# V-00808-00.net
KiCad netlist of a schematic drawn in EAGLE
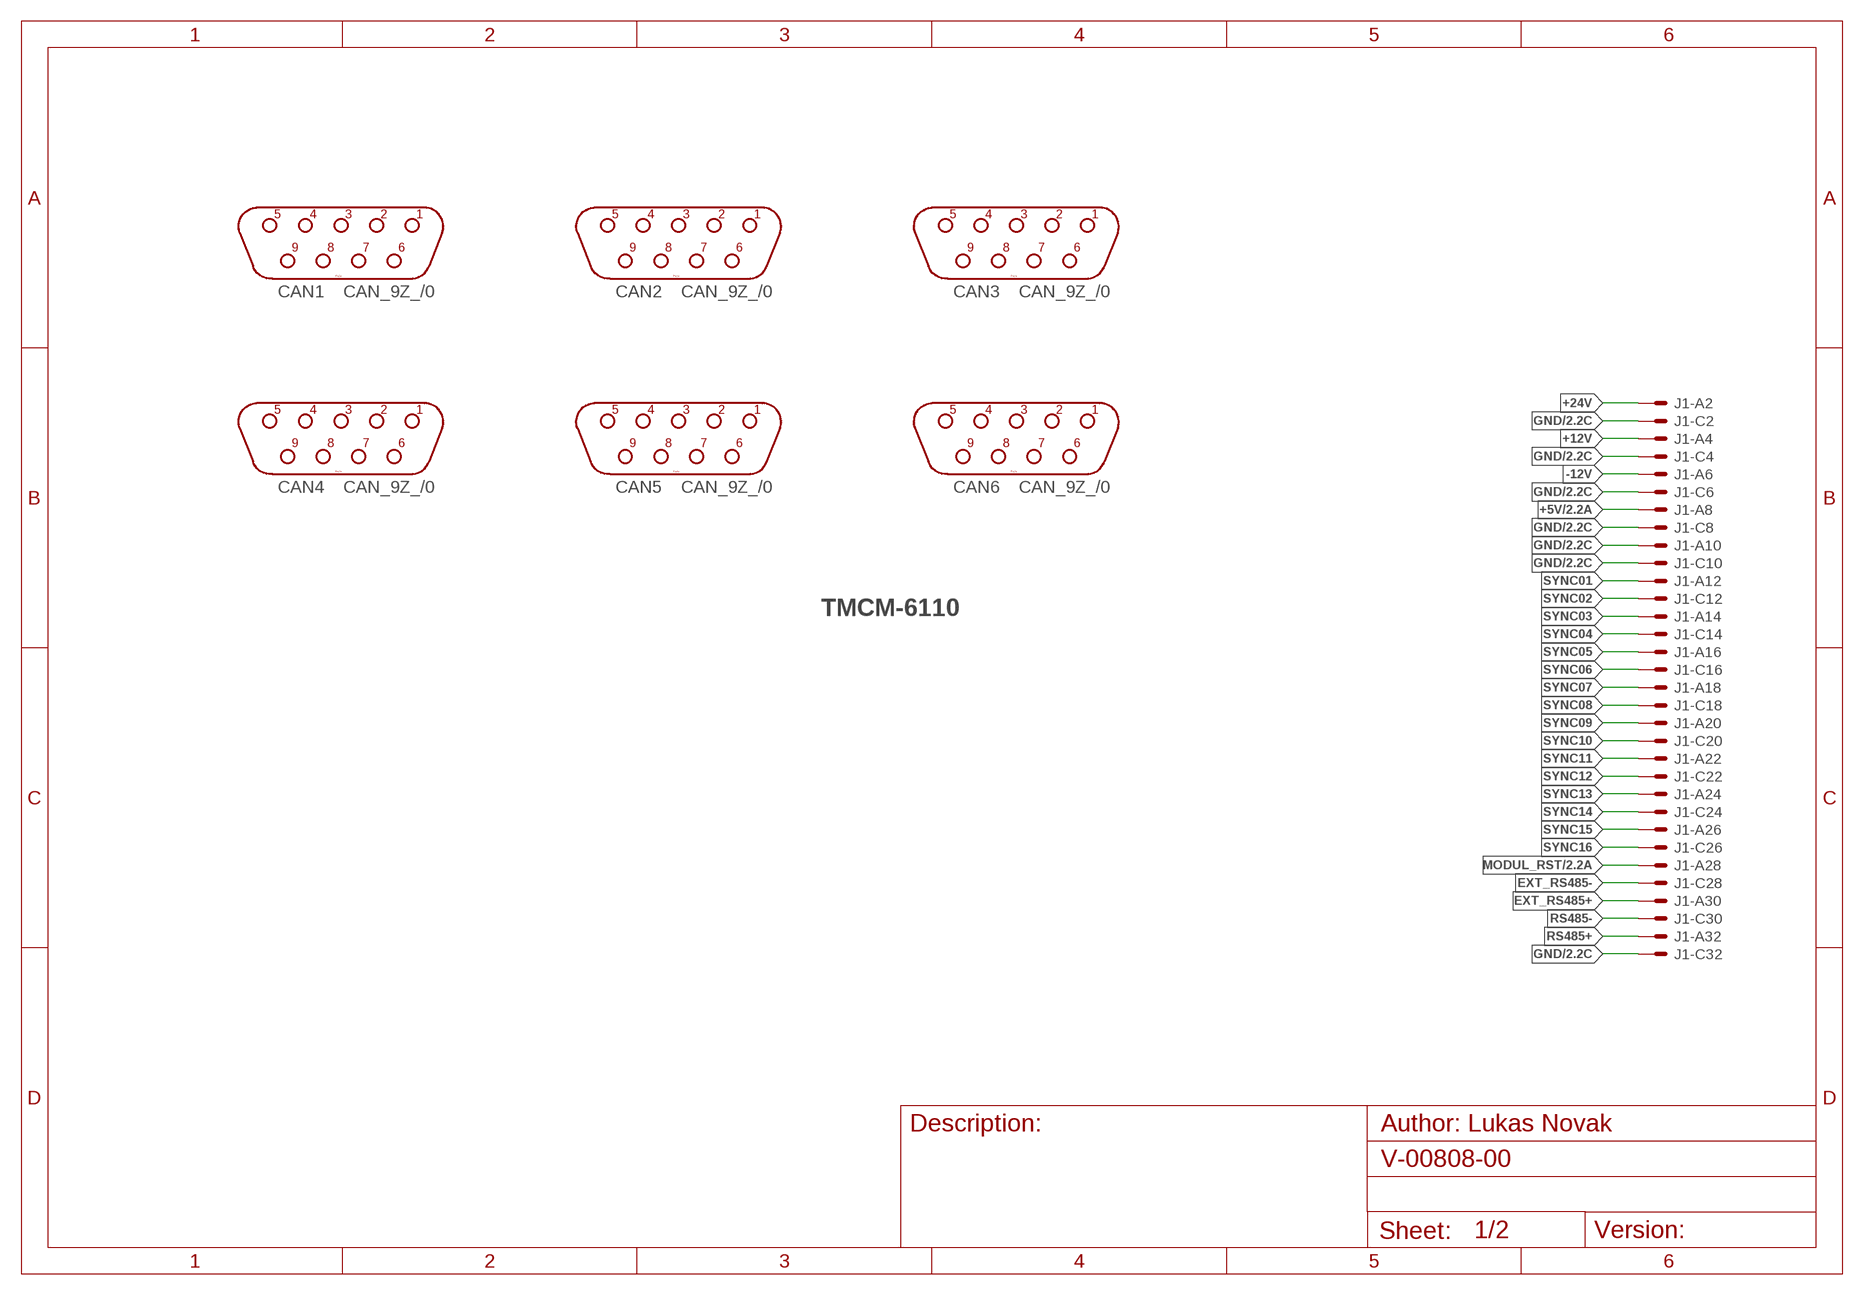
[diagram p0: schematic, sheet 1]
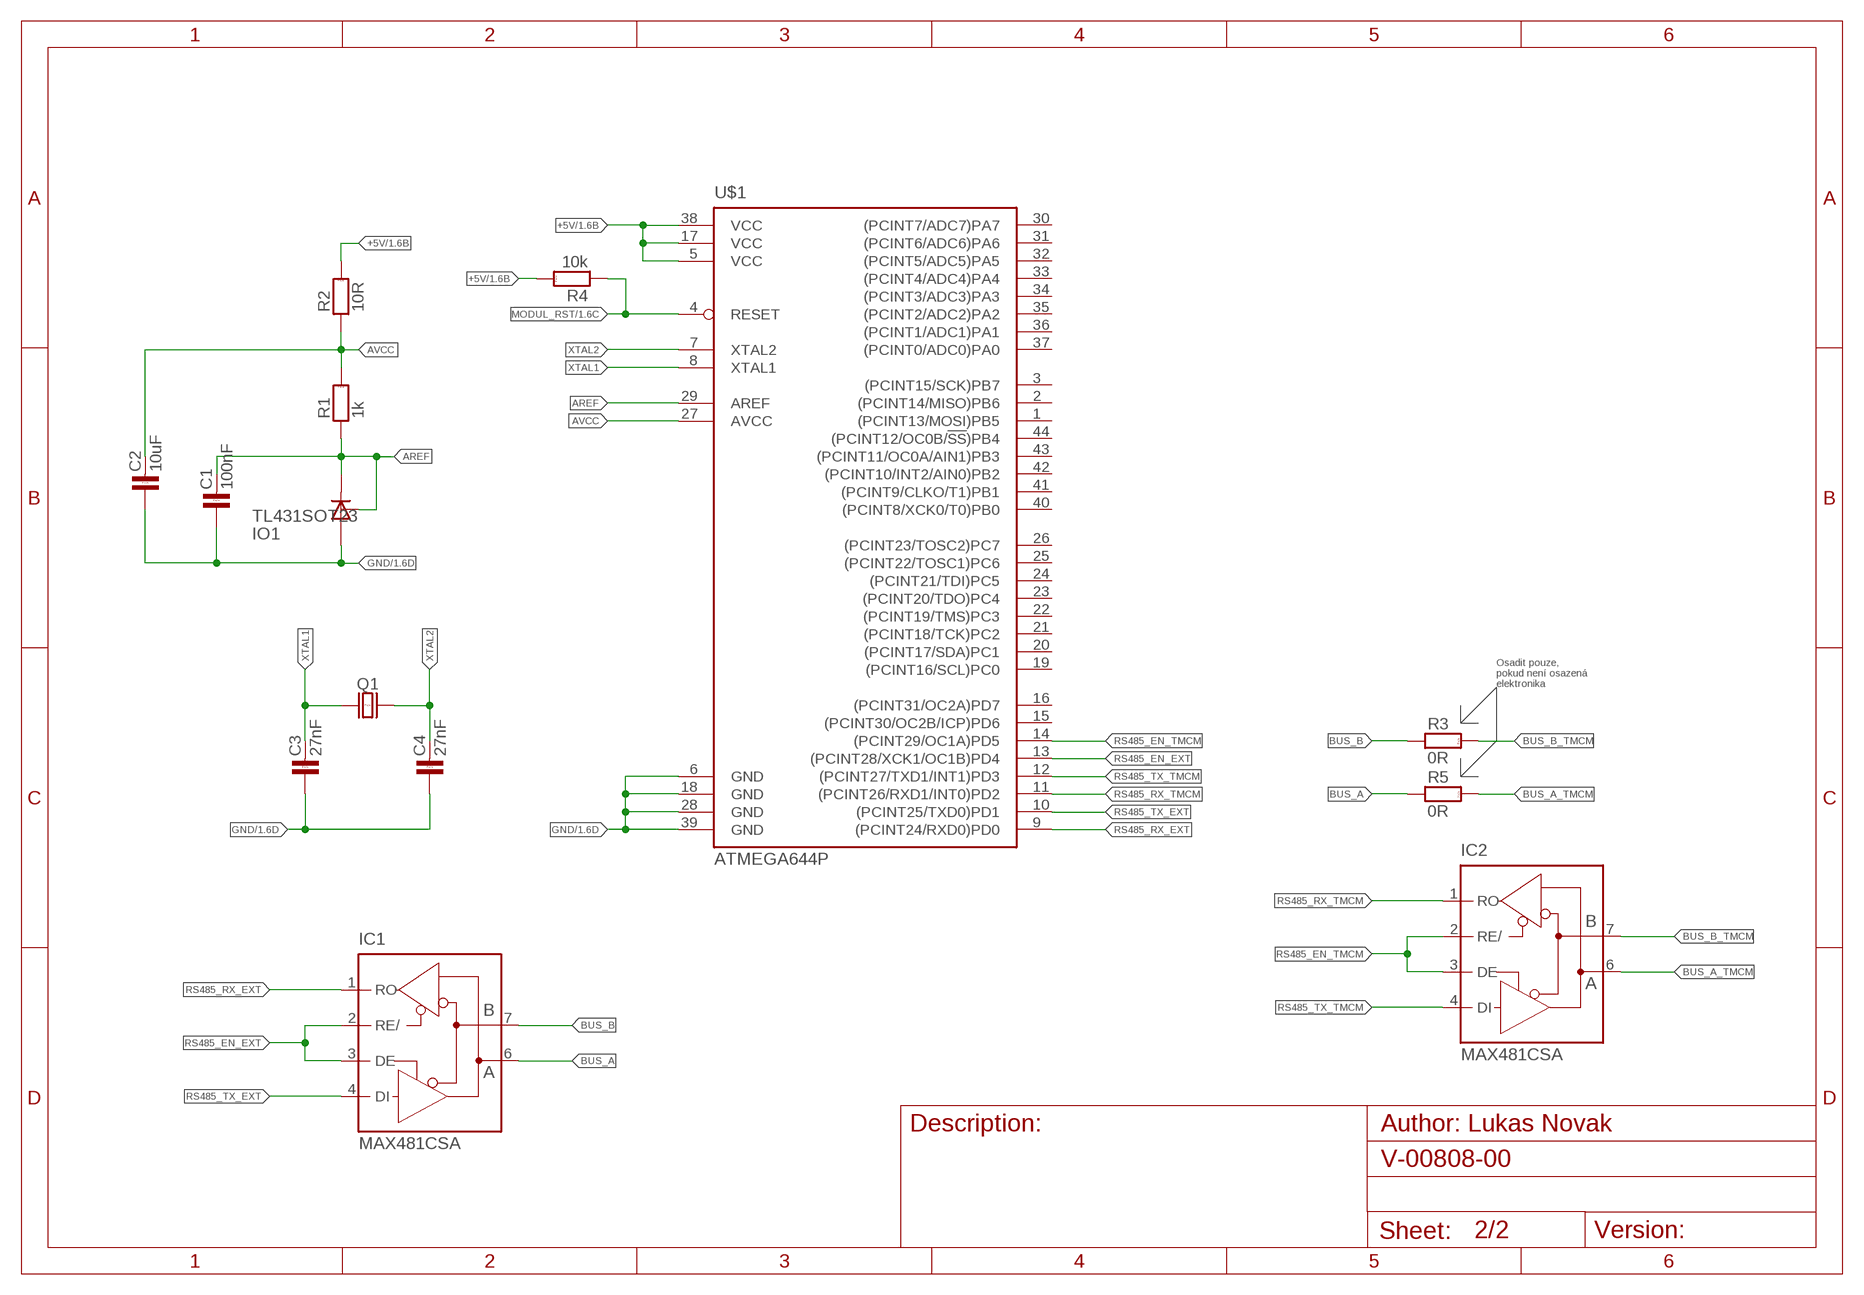
[diagram p1: schematic, sheet 2]

(export (version "E")
  (design (tool "Eeschema 10.0.6"))
  (components
    (comp (ref "C1")
      (value "100nF")
      (footprint "eagle-import:1206")
      (libsource (lib "eagle-import") (part "C-KER_1206"))
    )
    (comp (ref "C2")
      (value "10uF")
      (footprint "eagle-import:1206")
      (libsource (lib "eagle-import") (part "C-KER_1206"))
    )
    (comp (ref "C3")
      (value "27nF")
      (footprint "eagle-import:0805")
      (libsource (lib "eagle-import") (part "C-KER_0805"))
    )
    (comp (ref "C4")
      (value "27nF")
      (footprint "eagle-import:0805")
      (libsource (lib "eagle-import") (part "C-KER_0805"))
    )
    (comp (ref "IC1")
      (value "MAX481CSA")
      (footprint "eagle-import:SO08")
      (fields (field (name "MF") "MAXIM"))
      (libsource (lib "eagle-import") (part "MAX481CSA"))
    )
    (comp (ref "IC2")
      (value "MAX481CSA")
      (footprint "eagle-import:SO08")
      (fields (field (name "MF") "MAXIM"))
      (libsource (lib "eagle-import") (part "MAX481CSA"))
    )
    (comp (ref "IO1")
      (value "TL431SOT23")
      (footprint "eagle-import:SOT23")
      (fields (field (name "MPN") "TL431BFDT"))
      (libsource (lib "eagle-import") (part "TL431SOT23"))
    )
    (comp (ref "Q1")
      (value "Q_HC-49U")
      (footprint "eagle-import:HC-49U")
      (libsource (lib "eagle-import") (part "Q_HC-49U"))
    )
    (comp (ref "R1")
      (value "1k")
      (footprint "eagle-import:1206")
      (libsource (lib "eagle-import") (part "R_1206"))
    )
    (comp (ref "R2")
      (value "10R")
      (footprint "eagle-import:1206")
      (libsource (lib "eagle-import") (part "R_1206"))
    )
    (comp (ref "R3")
      (value "0R")
      (footprint "eagle-import:1206")
      (libsource (lib "eagle-import") (part "R_1206"))
    )
    (comp (ref "R4")
      (value "10k")
      (footprint "eagle-import:1206")
      (libsource (lib "eagle-import") (part "R_1206"))
    )
    (comp (ref "R5")
      (value "0R")
      (footprint "eagle-import:1206")
      (libsource (lib "eagle-import") (part "R_1206"))
    )
    (comp (ref "U$1")
      (value "ATMEGA644P")
      (footprint "eagle-import:TQFP44")
      (libsource (lib "eagle-import") (part "ATMEGA644P"))
    )
    (comp (ref "CAN1")
      (value "CAN_9Z_/0")
      (footprint "eagle-import:CAN9Z")
      (libsource (lib "eagle-import") (part "CAN_9Z_/0"))
    )
    (comp (ref "CAN2")
      (value "CAN_9Z_/0")
      (footprint "eagle-import:CAN9Z")
      (libsource (lib "eagle-import") (part "CAN_9Z_/0"))
    )
    (comp (ref "CAN3")
      (value "CAN_9Z_/0")
      (footprint "eagle-import:CAN9Z")
      (libsource (lib "eagle-import") (part "CAN_9Z_/0"))
    )
    (comp (ref "CAN4")
      (value "CAN_9Z_/0")
      (footprint "eagle-import:CAN9Z")
      (libsource (lib "eagle-import") (part "CAN_9Z_/0"))
    )
    (comp (ref "CAN5")
      (value "CAN_9Z_/0")
      (footprint "eagle-import:CAN9Z")
      (libsource (lib "eagle-import") (part "CAN_9Z_/0"))
    )
    (comp (ref "CAN6")
      (value "CAN_9Z_/0")
      (footprint "eagle-import:CAN9Z")
      (libsource (lib "eagle-import") (part "CAN_9Z_/0"))
    )
    (comp (ref "J1")
      (value "VG32SP")
      (footprint "eagle-import:VG32P")
      (libsource (lib "eagle-import") (part "VG32SP"))
    )
  )
  (nets
    (net (code "1") (name "+5V") (class "Default")
      (node (ref "J1") (pin "A8") (pinfunction "MS_A8") (pintype "passive"))
      (node (ref "R2") (pin "2") (pinfunction "2_2") (pintype "passive"))
      (node (ref "R4") (pin "2") (pinfunction "2_2") (pintype "passive"))
      (node (ref "U$1") (pin "17") (pinfunction "VCC_17") (pintype "power_in"))
      (node (ref "U$1") (pin "38") (pinfunction "VCC_38") (pintype "power_in"))
      (node (ref "U$1") (pin "5") (pinfunction "VCC_5") (pintype "power_in"))
    )
    (net (code "2") (name "+12V") (class "Default")
      (node (ref "J1") (pin "A4") (pinfunction "MS_A4") (pintype "passive"))
    )
    (net (code "3") (name "+24V") (class "Default")
      (node (ref "J1") (pin "A2") (pinfunction "MS_A2") (pintype "passive"))
    )
    (net (code "4") (name "-12V") (class "Default")
      (node (ref "J1") (pin "A6") (pinfunction "MS_A6") (pintype "passive"))
    )
    (net (code "5") (name "AREF") (class "Default")
      (node (ref "C1") (pin "2") (pinfunction "2_2") (pintype "passive"))
      (node (ref "IO1") (pin "1") (pinfunction "C_1") (pintype "bidirectional"))
      (node (ref "IO1") (pin "2") (pinfunction "R_2") (pintype "bidirectional"))
      (node (ref "R1") (pin "1") (pinfunction "1_1") (pintype "passive"))
      (node (ref "U$1") (pin "29") (pinfunction "AREF_29") (pintype "passive"))
    )
    (net (code "6") (name "AVCC") (class "Default")
      (node (ref "C2") (pin "2") (pinfunction "2_2") (pintype "passive"))
      (node (ref "R1") (pin "2") (pinfunction "2_2") (pintype "passive"))
      (node (ref "R2") (pin "1") (pinfunction "1_1") (pintype "passive"))
      (node (ref "U$1") (pin "27") (pinfunction "AVCC_27") (pintype "power_in"))
    )
    (net (code "7") (name "BUS_A") (class "Default")
      (node (ref "IC1") (pin "6") (pinfunction "A_6") (pintype "passive"))
      (node (ref "R5") (pin "1") (pinfunction "1_1") (pintype "passive"))
    )
    (net (code "8") (name "BUS_A_TMCM") (class "Default")
      (node (ref "IC2") (pin "6") (pinfunction "A_6") (pintype "passive"))
      (node (ref "R5") (pin "2") (pinfunction "2_2") (pintype "passive"))
    )
    (net (code "9") (name "BUS_B") (class "Default")
      (node (ref "IC1") (pin "7") (pinfunction "B_7") (pintype "passive"))
      (node (ref "R3") (pin "1") (pinfunction "1_1") (pintype "passive"))
    )
    (net (code "10") (name "BUS_B_TMCM") (class "Default")
      (node (ref "IC2") (pin "7") (pinfunction "B_7") (pintype "passive"))
      (node (ref "R3") (pin "2") (pinfunction "2_2") (pintype "passive"))
    )
    (net (code "11") (name "EXT_RS485+") (class "Default")
      (node (ref "J1") (pin "A30") (pinfunction "MS_A30") (pintype "passive"))
    )
    (net (code "12") (name "EXT_RS485-") (class "Default")
      (node (ref "J1") (pin "C28") (pinfunction "MS_C28") (pintype "passive"))
    )
    (net (code "13") (name "GND") (class "Default")
      (node (ref "C1") (pin "1") (pinfunction "1_1") (pintype "passive"))
      (node (ref "C2") (pin "1") (pinfunction "1_1") (pintype "passive"))
      (node (ref "C3") (pin "1") (pinfunction "1_1") (pintype "passive"))
      (node (ref "C4") (pin "1") (pinfunction "1_1") (pintype "passive"))
      (node (ref "IO1") (pin "3") (pinfunction "A_3") (pintype "bidirectional"))
      (node (ref "J1") (pin "A10") (pinfunction "MS_A10") (pintype "passive"))
      (node (ref "J1") (pin "C10") (pinfunction "MS_C10") (pintype "passive"))
      (node (ref "J1") (pin "C2") (pinfunction "MS_C2") (pintype "passive"))
      (node (ref "J1") (pin "C32") (pinfunction "MSV_C32") (pintype "passive"))
      (node (ref "J1") (pin "C4") (pinfunction "MS_C4") (pintype "passive"))
      (node (ref "J1") (pin "C6") (pinfunction "MS_C6") (pintype "passive"))
      (node (ref "J1") (pin "C8") (pinfunction "MS_C8") (pintype "passive"))
      (node (ref "U$1") (pin "18") (pinfunction "GND_18") (pintype "power_in"))
      (node (ref "U$1") (pin "28") (pinfunction "GND_28") (pintype "power_in"))
      (node (ref "U$1") (pin "39") (pinfunction "GND_39") (pintype "power_in"))
      (node (ref "U$1") (pin "6") (pinfunction "GND_6") (pintype "power_in"))
    )
    (net (code "14") (name "MODUL_RST") (class "Default")
      (node (ref "J1") (pin "A28") (pinfunction "MS_A28") (pintype "passive"))
      (node (ref "R4") (pin "1") (pinfunction "1_1") (pintype "passive"))
      (node (ref "U$1") (pin "4") (pinfunction "RESET_4") (pintype "input"))
    )
    (net (code "15") (name "RS485+") (class "Default")
      (node (ref "J1") (pin "A32") (pinfunction "MS_A32") (pintype "passive"))
    )
    (net (code "16") (name "RS485-") (class "Default")
      (node (ref "J1") (pin "C30") (pinfunction "MS_C30") (pintype "passive"))
    )
    (net (code "17") (name "RS485_EN_EXT") (class "Default")
      (node (ref "IC1") (pin "2") (pinfunction "RE/_2") (pintype "input"))
      (node (ref "IC1") (pin "3") (pinfunction "DE_3") (pintype "input"))
      (node (ref "U$1") (pin "13") (pinfunction "(PCINT28/XCK1/OC1B)PD4_13") (pintype "bidirectional"))
    )
    (net (code "18") (name "RS485_EN_TMCM") (class "Default")
      (node (ref "IC2") (pin "2") (pinfunction "RE/_2") (pintype "input"))
      (node (ref "IC2") (pin "3") (pinfunction "DE_3") (pintype "input"))
      (node (ref "U$1") (pin "14") (pinfunction "(PCINT29/OC1A)PD5_14") (pintype "bidirectional"))
    )
    (net (code "19") (name "RS485_RX_EXT") (class "Default")
      (node (ref "IC1") (pin "1") (pinfunction "RO_1") (pintype "output"))
      (node (ref "U$1") (pin "9") (pinfunction "(PCINT24/RXD0)PD0_9") (pintype "bidirectional"))
    )
    (net (code "20") (name "RS485_RX_TMCM") (class "Default")
      (node (ref "IC2") (pin "1") (pinfunction "RO_1") (pintype "output"))
      (node (ref "U$1") (pin "11") (pinfunction "(PCINT26/RXD1/INT0)PD2_11") (pintype "bidirectional"))
    )
    (net (code "21") (name "RS485_TX_EXT") (class "Default")
      (node (ref "IC1") (pin "4") (pinfunction "DI_4") (pintype "input"))
      (node (ref "U$1") (pin "10") (pinfunction "(PCINT25/TXD0)PD1_10") (pintype "bidirectional"))
    )
    (net (code "22") (name "RS485_TX_TMCM") (class "Default")
      (node (ref "IC2") (pin "4") (pinfunction "DI_4") (pintype "input"))
      (node (ref "U$1") (pin "12") (pinfunction "(PCINT27/TXD1/INT1)PD3_12") (pintype "bidirectional"))
    )
    (net (code "23") (name "SYNC01") (class "Default")
      (node (ref "J1") (pin "A12") (pinfunction "MS_A12") (pintype "passive"))
    )
    (net (code "24") (name "SYNC02") (class "Default")
      (node (ref "J1") (pin "C12") (pinfunction "MS_C12") (pintype "passive"))
    )
    (net (code "25") (name "SYNC03") (class "Default")
      (node (ref "J1") (pin "A14") (pinfunction "MS_A14") (pintype "passive"))
    )
    (net (code "26") (name "SYNC04") (class "Default")
      (node (ref "J1") (pin "C14") (pinfunction "MS_C14") (pintype "passive"))
    )
    (net (code "27") (name "SYNC05") (class "Default")
      (node (ref "J1") (pin "A16") (pinfunction "MS_A16") (pintype "passive"))
    )
    (net (code "28") (name "SYNC06") (class "Default")
      (node (ref "J1") (pin "C16") (pinfunction "MS_C16") (pintype "passive"))
    )
    (net (code "29") (name "SYNC07") (class "Default")
      (node (ref "J1") (pin "A18") (pinfunction "MS_A18") (pintype "passive"))
    )
    (net (code "30") (name "SYNC08") (class "Default")
      (node (ref "J1") (pin "C18") (pinfunction "MS_C18") (pintype "passive"))
    )
    (net (code "31") (name "SYNC09") (class "Default")
      (node (ref "J1") (pin "A20") (pinfunction "MS_A20") (pintype "passive"))
    )
    (net (code "32") (name "SYNC10") (class "Default")
      (node (ref "J1") (pin "C20") (pinfunction "MS_C20") (pintype "passive"))
    )
    (net (code "33") (name "SYNC11") (class "Default")
      (node (ref "J1") (pin "A22") (pinfunction "MS_A22") (pintype "passive"))
    )
    (net (code "34") (name "SYNC12") (class "Default")
      (node (ref "J1") (pin "C22") (pinfunction "MS_C22") (pintype "passive"))
    )
    (net (code "35") (name "SYNC13") (class "Default")
      (node (ref "J1") (pin "A24") (pinfunction "MS_A24") (pintype "passive"))
    )
    (net (code "36") (name "SYNC14") (class "Default")
      (node (ref "J1") (pin "C24") (pinfunction "MS_C24") (pintype "passive"))
    )
    (net (code "37") (name "SYNC15") (class "Default")
      (node (ref "J1") (pin "A26") (pinfunction "MS_A26") (pintype "passive"))
    )
    (net (code "38") (name "SYNC16") (class "Default")
      (node (ref "J1") (pin "C26") (pinfunction "MS_C26") (pintype "passive"))
    )
    (net (code "39") (name "XTAL1") (class "Default")
      (node (ref "C3") (pin "2") (pinfunction "2_2") (pintype "passive"))
      (node (ref "Q1") (pin "1") (pinfunction "1_1") (pintype "passive"))
      (node (ref "U$1") (pin "8") (pinfunction "XTAL1_8") (pintype "bidirectional"))
    )
    (net (code "40") (name "XTAL2") (class "Default")
      (node (ref "C4") (pin "2") (pinfunction "2_2") (pintype "passive"))
      (node (ref "Q1") (pin "2") (pinfunction "2_2") (pintype "passive"))
      (node (ref "U$1") (pin "7") (pinfunction "XTAL2_7") (pintype "bidirectional"))
    )
    (net (code "41") (name "unconnected-(CAN1-Pad1)") (class "Default")
      (node (ref "CAN1") (pin "1") (pinfunction "1_1") (pintype "passive"))
    )
    (net (code "42") (name "unconnected-(CAN1-Pad2)") (class "Default")
      (node (ref "CAN1") (pin "2") (pinfunction "2_2") (pintype "passive"))
    )
    (net (code "43") (name "unconnected-(CAN1-Pad3)") (class "Default")
      (node (ref "CAN1") (pin "3") (pinfunction "3_3") (pintype "passive"))
    )
    (net (code "44") (name "unconnected-(CAN1-Pad4)") (class "Default")
      (node (ref "CAN1") (pin "4") (pinfunction "4_4") (pintype "passive"))
    )
    (net (code "45") (name "unconnected-(CAN1-Pad5)") (class "Default")
      (node (ref "CAN1") (pin "5") (pinfunction "5_5") (pintype "passive"))
    )
    (net (code "46") (name "unconnected-(CAN1-Pad6)") (class "Default")
      (node (ref "CAN1") (pin "6") (pinfunction "6_6") (pintype "passive"))
    )
    (net (code "47") (name "unconnected-(CAN1-Pad7)") (class "Default")
      (node (ref "CAN1") (pin "7") (pinfunction "7_7") (pintype "passive"))
    )
    (net (code "48") (name "unconnected-(CAN1-Pad8)") (class "Default")
      (node (ref "CAN1") (pin "8") (pinfunction "8_8") (pintype "passive"))
    )
    (net (code "49") (name "unconnected-(CAN1-Pad9)") (class "Default")
      (node (ref "CAN1") (pin "9") (pinfunction "9_9") (pintype "passive"))
    )
    (net (code "50") (name "unconnected-(CAN2-Pad1)") (class "Default")
      (node (ref "CAN2") (pin "1") (pinfunction "1_1") (pintype "passive"))
    )
    (net (code "51") (name "unconnected-(CAN2-Pad2)") (class "Default")
      (node (ref "CAN2") (pin "2") (pinfunction "2_2") (pintype "passive"))
    )
    (net (code "52") (name "unconnected-(CAN2-Pad3)") (class "Default")
      (node (ref "CAN2") (pin "3") (pinfunction "3_3") (pintype "passive"))
    )
    (net (code "53") (name "unconnected-(CAN2-Pad4)") (class "Default")
      (node (ref "CAN2") (pin "4") (pinfunction "4_4") (pintype "passive"))
    )
    (net (code "54") (name "unconnected-(CAN2-Pad5)") (class "Default")
      (node (ref "CAN2") (pin "5") (pinfunction "5_5") (pintype "passive"))
    )
    (net (code "55") (name "unconnected-(CAN2-Pad6)") (class "Default")
      (node (ref "CAN2") (pin "6") (pinfunction "6_6") (pintype "passive"))
    )
    (net (code "56") (name "unconnected-(CAN2-Pad7)") (class "Default")
      (node (ref "CAN2") (pin "7") (pinfunction "7_7") (pintype "passive"))
    )
    (net (code "57") (name "unconnected-(CAN2-Pad8)") (class "Default")
      (node (ref "CAN2") (pin "8") (pinfunction "8_8") (pintype "passive"))
    )
    (net (code "58") (name "unconnected-(CAN2-Pad9)") (class "Default")
      (node (ref "CAN2") (pin "9") (pinfunction "9_9") (pintype "passive"))
    )
    (net (code "59") (name "unconnected-(CAN3-Pad1)") (class "Default")
      (node (ref "CAN3") (pin "1") (pinfunction "1_1") (pintype "passive"))
    )
    (net (code "60") (name "unconnected-(CAN3-Pad2)") (class "Default")
      (node (ref "CAN3") (pin "2") (pinfunction "2_2") (pintype "passive"))
    )
    (net (code "61") (name "unconnected-(CAN3-Pad3)") (class "Default")
      (node (ref "CAN3") (pin "3") (pinfunction "3_3") (pintype "passive"))
    )
    (net (code "62") (name "unconnected-(CAN3-Pad4)") (class "Default")
      (node (ref "CAN3") (pin "4") (pinfunction "4_4") (pintype "passive"))
    )
    (net (code "63") (name "unconnected-(CAN3-Pad5)") (class "Default")
      (node (ref "CAN3") (pin "5") (pinfunction "5_5") (pintype "passive"))
    )
    (net (code "64") (name "unconnected-(CAN3-Pad6)") (class "Default")
      (node (ref "CAN3") (pin "6") (pinfunction "6_6") (pintype "passive"))
    )
    (net (code "65") (name "unconnected-(CAN3-Pad7)") (class "Default")
      (node (ref "CAN3") (pin "7") (pinfunction "7_7") (pintype "passive"))
    )
    (net (code "66") (name "unconnected-(CAN3-Pad8)") (class "Default")
      (node (ref "CAN3") (pin "8") (pinfunction "8_8") (pintype "passive"))
    )
    (net (code "67") (name "unconnected-(CAN3-Pad9)") (class "Default")
      (node (ref "CAN3") (pin "9") (pinfunction "9_9") (pintype "passive"))
    )
    (net (code "68") (name "unconnected-(CAN4-Pad1)") (class "Default")
      (node (ref "CAN4") (pin "1") (pinfunction "1_1") (pintype "passive"))
    )
    (net (code "69") (name "unconnected-(CAN4-Pad2)") (class "Default")
      (node (ref "CAN4") (pin "2") (pinfunction "2_2") (pintype "passive"))
    )
    (net (code "70") (name "unconnected-(CAN4-Pad3)") (class "Default")
      (node (ref "CAN4") (pin "3") (pinfunction "3_3") (pintype "passive"))
    )
    (net (code "71") (name "unconnected-(CAN4-Pad4)") (class "Default")
      (node (ref "CAN4") (pin "4") (pinfunction "4_4") (pintype "passive"))
    )
    (net (code "72") (name "unconnected-(CAN4-Pad5)") (class "Default")
      (node (ref "CAN4") (pin "5") (pinfunction "5_5") (pintype "passive"))
    )
    (net (code "73") (name "unconnected-(CAN4-Pad6)") (class "Default")
      (node (ref "CAN4") (pin "6") (pinfunction "6_6") (pintype "passive"))
    )
    (net (code "74") (name "unconnected-(CAN4-Pad7)") (class "Default")
      (node (ref "CAN4") (pin "7") (pinfunction "7_7") (pintype "passive"))
    )
    (net (code "75") (name "unconnected-(CAN4-Pad8)") (class "Default")
      (node (ref "CAN4") (pin "8") (pinfunction "8_8") (pintype "passive"))
    )
    (net (code "76") (name "unconnected-(CAN4-Pad9)") (class "Default")
      (node (ref "CAN4") (pin "9") (pinfunction "9_9") (pintype "passive"))
    )
    (net (code "77") (name "unconnected-(CAN5-Pad1)") (class "Default")
      (node (ref "CAN5") (pin "1") (pinfunction "1_1") (pintype "passive"))
    )
    (net (code "78") (name "unconnected-(CAN5-Pad2)") (class "Default")
      (node (ref "CAN5") (pin "2") (pinfunction "2_2") (pintype "passive"))
    )
    (net (code "79") (name "unconnected-(CAN5-Pad3)") (class "Default")
      (node (ref "CAN5") (pin "3") (pinfunction "3_3") (pintype "passive"))
    )
    (net (code "80") (name "unconnected-(CAN5-Pad4)") (class "Default")
      (node (ref "CAN5") (pin "4") (pinfunction "4_4") (pintype "passive"))
    )
    (net (code "81") (name "unconnected-(CAN5-Pad5)") (class "Default")
      (node (ref "CAN5") (pin "5") (pinfunction "5_5") (pintype "passive"))
    )
    (net (code "82") (name "unconnected-(CAN5-Pad6)") (class "Default")
      (node (ref "CAN5") (pin "6") (pinfunction "6_6") (pintype "passive"))
    )
    (net (code "83") (name "unconnected-(CAN5-Pad7)") (class "Default")
      (node (ref "CAN5") (pin "7") (pinfunction "7_7") (pintype "passive"))
    )
    (net (code "84") (name "unconnected-(CAN5-Pad8)") (class "Default")
      (node (ref "CAN5") (pin "8") (pinfunction "8_8") (pintype "passive"))
    )
    (net (code "85") (name "unconnected-(CAN5-Pad9)") (class "Default")
      (node (ref "CAN5") (pin "9") (pinfunction "9_9") (pintype "passive"))
    )
    (net (code "86") (name "unconnected-(CAN6-Pad1)") (class "Default")
      (node (ref "CAN6") (pin "1") (pinfunction "1_1") (pintype "passive"))
    )
    (net (code "87") (name "unconnected-(CAN6-Pad2)") (class "Default")
      (node (ref "CAN6") (pin "2") (pinfunction "2_2") (pintype "passive"))
    )
    (net (code "88") (name "unconnected-(CAN6-Pad3)") (class "Default")
      (node (ref "CAN6") (pin "3") (pinfunction "3_3") (pintype "passive"))
    )
    (net (code "89") (name "unconnected-(CAN6-Pad4)") (class "Default")
      (node (ref "CAN6") (pin "4") (pinfunction "4_4") (pintype "passive"))
    )
    (net (code "90") (name "unconnected-(CAN6-Pad5)") (class "Default")
      (node (ref "CAN6") (pin "5") (pinfunction "5_5") (pintype "passive"))
    )
    (net (code "91") (name "unconnected-(CAN6-Pad6)") (class "Default")
      (node (ref "CAN6") (pin "6") (pinfunction "6_6") (pintype "passive"))
    )
    (net (code "92") (name "unconnected-(CAN6-Pad7)") (class "Default")
      (node (ref "CAN6") (pin "7") (pinfunction "7_7") (pintype "passive"))
    )
    (net (code "93") (name "unconnected-(CAN6-Pad8)") (class "Default")
      (node (ref "CAN6") (pin "8") (pinfunction "8_8") (pintype "passive"))
    )
    (net (code "94") (name "unconnected-(CAN6-Pad9)") (class "Default")
      (node (ref "CAN6") (pin "9") (pinfunction "9_9") (pintype "passive"))
    )
    (net (code "95") (name "unconnected-(U$1-(PCINT0{slash}ADC0)PA0-Pad37)") (class "Default")
      (node (ref "U$1") (pin "37") (pinfunction "(PCINT0/ADC0)PA0_37") (pintype "bidirectional"))
    )
    (net (code "96") (name "unconnected-(U$1-(PCINT1{slash}ADC1)PA1-Pad36)") (class "Default")
      (node (ref "U$1") (pin "36") (pinfunction "(PCINT1/ADC1)PA1_36") (pintype "bidirectional"))
    )
    (net (code "97") (name "unconnected-(U$1-(PCINT2{slash}ADC2)PA2-Pad35)") (class "Default")
      (node (ref "U$1") (pin "35") (pinfunction "(PCINT2/ADC2)PA2_35") (pintype "bidirectional"))
    )
    (net (code "98") (name "unconnected-(U$1-(PCINT3{slash}ADC3)PA3-Pad34)") (class "Default")
      (node (ref "U$1") (pin "34") (pinfunction "(PCINT3/ADC3)PA3_34") (pintype "bidirectional"))
    )
    (net (code "99") (name "unconnected-(U$1-(PCINT4{slash}ADC4)PA4-Pad33)") (class "Default")
      (node (ref "U$1") (pin "33") (pinfunction "(PCINT4/ADC4)PA4_33") (pintype "bidirectional"))
    )
    (net (code "100") (name "unconnected-(U$1-(PCINT5{slash}ADC5)PA5-Pad32)") (class "Default")
      (node (ref "U$1") (pin "32") (pinfunction "(PCINT5/ADC5)PA5_32") (pintype "bidirectional"))
    )
    (net (code "101") (name "unconnected-(U$1-(PCINT6{slash}ADC6)PA6-Pad31)") (class "Default")
      (node (ref "U$1") (pin "31") (pinfunction "(PCINT6/ADC6)PA6_31") (pintype "bidirectional"))
    )
    (net (code "102") (name "unconnected-(U$1-(PCINT7{slash}ADC7)PA7-Pad30)") (class "Default")
      (node (ref "U$1") (pin "30") (pinfunction "(PCINT7/ADC7)PA7_30") (pintype "bidirectional"))
    )
    (net (code "103") (name "unconnected-(U$1-(PCINT8{slash}XCK0{slash}T0)PB0-Pad40)") (class "Default")
      (node (ref "U$1") (pin "40") (pinfunction "(PCINT8/XCK0/T0)PB0_40") (pintype "bidirectional"))
    )
    (net (code "104") (name "unconnected-(U$1-(PCINT9{slash}CLKO{slash}T1)PB1-Pad41)") (class "Default")
      (node (ref "U$1") (pin "41") (pinfunction "(PCINT9/CLKO/T1)PB1_41") (pintype "bidirectional"))
    )
    (net (code "105") (name "unconnected-(U$1-(PCINT10{slash}INT2{slash}AIN0)PB2-Pad42)") (class "Default")
      (node (ref "U$1") (pin "42") (pinfunction "(PCINT10/INT2/AIN0)PB2_42") (pintype "bidirectional"))
    )
    (net (code "106") (name "unconnected-(U$1-(PCINT11{slash}OC0A{slash}AIN1)PB3-Pad43)") (class "Default")
      (node (ref "U$1") (pin "43") (pinfunction "(PCINT11/OC0A/AIN1)PB3_43") (pintype "bidirectional"))
    )
    (net (code "107") (name "unconnected-(U$1-(PCINT12{slash}OC0B{slash}~{SS})PB4-Pad44)") (class "Default")
      (node (ref "U$1") (pin "44") (pinfunction "(PCINT12/OC0B/~{SS})PB4_44") (pintype "bidirectional"))
    )
    (net (code "108") (name "unconnected-(U$1-(PCINT13{slash}MOSI)PB5-Pad1)") (class "Default")
      (node (ref "U$1") (pin "1") (pinfunction "(PCINT13/MOSI)PB5_1") (pintype "bidirectional"))
    )
    (net (code "109") (name "unconnected-(U$1-(PCINT14{slash}MISO)PB6-Pad2)") (class "Default")
      (node (ref "U$1") (pin "2") (pinfunction "(PCINT14/MISO)PB6_2") (pintype "bidirectional"))
    )
    (net (code "110") (name "unconnected-(U$1-(PCINT15{slash}SCK)PB7-Pad3)") (class "Default")
      (node (ref "U$1") (pin "3") (pinfunction "(PCINT15/SCK)PB7_3") (pintype "bidirectional"))
    )
    (net (code "111") (name "unconnected-(U$1-(PCINT16{slash}SCL)PC0-Pad19)") (class "Default")
      (node (ref "U$1") (pin "19") (pinfunction "(PCINT16/SCL)PC0_19") (pintype "output"))
    )
    (net (code "112") (name "unconnected-(U$1-(PCINT17{slash}SDA)PC1-Pad20)") (class "Default")
      (node (ref "U$1") (pin "20") (pinfunction "(PCINT17/SDA)PC1_20") (pintype "output"))
    )
    (net (code "113") (name "unconnected-(U$1-(PCINT18{slash}TCK)PC2-Pad21)") (class "Default")
      (node (ref "U$1") (pin "21") (pinfunction "(PCINT18/TCK)PC2_21") (pintype "output"))
    )
    (net (code "114") (name "unconnected-(U$1-(PCINT19{slash}TMS)PC3-Pad22)") (class "Default")
      (node (ref "U$1") (pin "22") (pinfunction "(PCINT19/TMS)PC3_22") (pintype "output"))
    )
    (net (code "115") (name "unconnected-(U$1-(PCINT20{slash}TDO)PC4-Pad23)") (class "Default")
      (node (ref "U$1") (pin "23") (pinfunction "(PCINT20/TDO)PC4_23") (pintype "output"))
    )
    (net (code "116") (name "unconnected-(U$1-(PCINT21{slash}TDI)PC5-Pad24)") (class "Default")
      (node (ref "U$1") (pin "24") (pinfunction "(PCINT21/TDI)PC5_24") (pintype "output"))
    )
    (net (code "117") (name "unconnected-(U$1-(PCINT22{slash}TOSC1)PC6-Pad25)") (class "Default")
      (node (ref "U$1") (pin "25") (pinfunction "(PCINT22/TOSC1)PC6_25") (pintype "output"))
    )
    (net (code "118") (name "unconnected-(U$1-(PCINT23{slash}TOSC2)PC7-Pad26)") (class "Default")
      (node (ref "U$1") (pin "26") (pinfunction "(PCINT23/TOSC2)PC7_26") (pintype "output"))
    )
    (net (code "119") (name "unconnected-(U$1-(PCINT30{slash}OC2B{slash}ICP)PD6-Pad15)") (class "Default")
      (node (ref "U$1") (pin "15") (pinfunction "(PCINT30/OC2B/ICP)PD6_15") (pintype "bidirectional"))
    )
    (net (code "120") (name "unconnected-(U$1-(PCINT31{slash}OC2A)PD7-Pad16)") (class "Default")
      (node (ref "U$1") (pin "16") (pinfunction "(PCINT31/OC2A)PD7_16") (pintype "bidirectional"))
    )
  )
)
